# TiltSensor.net
KiCad netlist of a schematic drawn in EAGLE
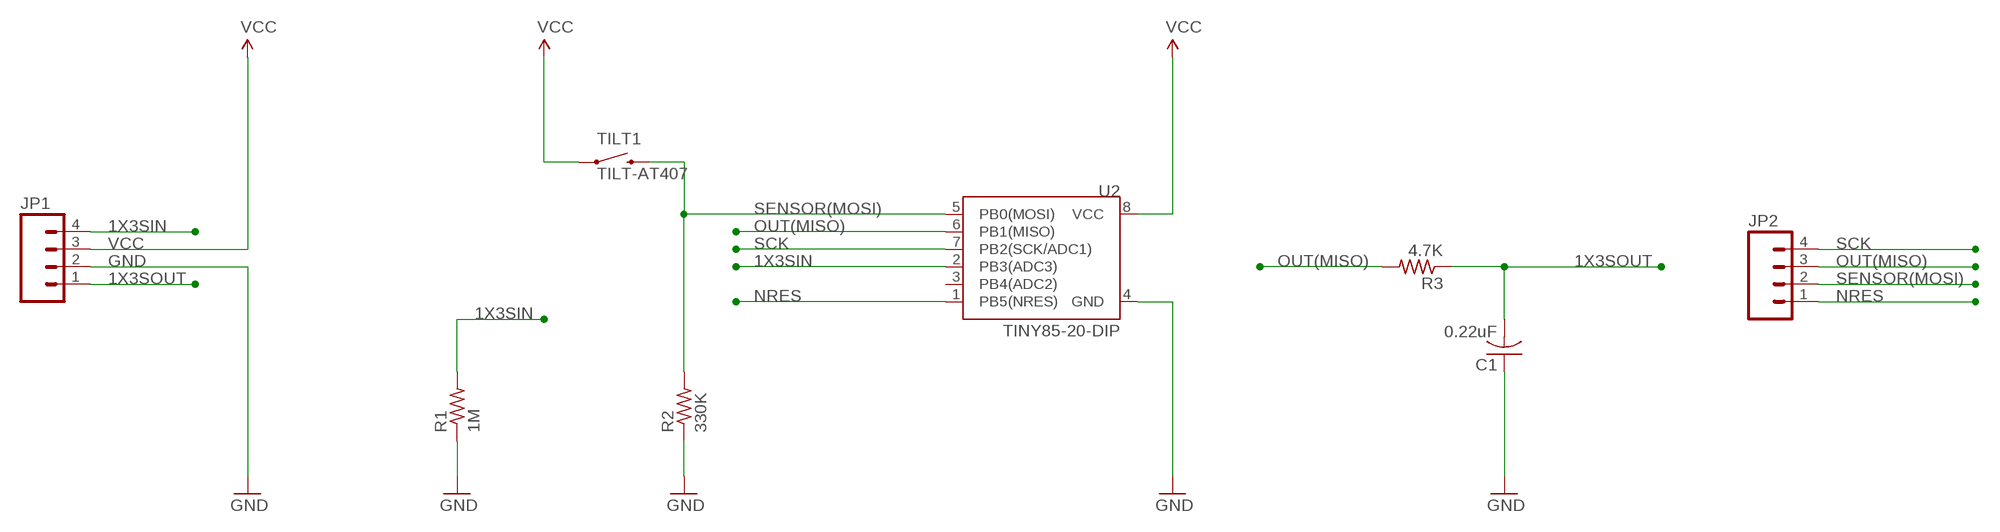
[diagram p0: schematic, sheet 1]

(export (version "E")
  (design (tool "Eeschema 10.0.6"))
  (components
    (comp (ref "C1")
      (value "0.22uF")
      (footprint "eagle-import:C0402")
      (libsource (lib "eagle-import") (part "C-USC0402"))
    )
    (comp (ref "JP1")
      (value "M04PTH")
      (footprint "eagle-import:1X04")
      (libsource (lib "eagle-import") (part "M04PTH"))
    )
    (comp (ref "JP2")
      (value "M04PTH")
      (footprint "eagle-import:1X04")
      (libsource (lib "eagle-import") (part "M04PTH"))
    )
    (comp (ref "R1")
      (value "1M")
      (footprint "eagle-import:R0603")
      (libsource (lib "eagle-import") (part "R-US_R0603"))
    )
    (comp (ref "R2")
      (value "330K")
      (footprint "eagle-import:R0603")
      (libsource (lib "eagle-import") (part "R-US_R0603"))
    )
    (comp (ref "R3")
      (value "4.7K")
      (footprint "eagle-import:R0603")
      (libsource (lib "eagle-import") (part "R-US_R0603"))
    )
    (comp (ref "TILT1")
      (value "TILT-AT407")
      (footprint "eagle-import:TILT-AT407")
      (libsource (lib "eagle-import") (part "TILT-AT407"))
    )
    (comp (ref "U2")
      (value "TINY85-20-DIP")
      (footprint "eagle-import:DIP08")
      (libsource (lib "eagle-import") (part "ATTINY45TINY85-20-DIP"))
    )
  )
  (nets
    (net (code "1") (name "/1X3SIN") (class "Default")
      (node (ref "JP1") (pin "4") (pinfunction "4_4") (pintype "passive"))
      (node (ref "R1") (pin "2") (pinfunction "2_2") (pintype "passive"))
      (node (ref "U2") (pin "2") (pinfunction "PB3(ADC3)_2") (pintype "bidirectional"))
    )
    (net (code "2") (name "/1X3SOUT") (class "Default")
      (node (ref "C1") (pin "2") (pinfunction "2_2") (pintype "passive"))
      (node (ref "JP1") (pin "1") (pinfunction "1_1") (pintype "passive"))
      (node (ref "R3") (pin "1") (pinfunction "1_1") (pintype "passive"))
    )
    (net (code "3") (name "/NRES") (class "Default")
      (node (ref "JP2") (pin "1") (pinfunction "1_1") (pintype "passive"))
      (node (ref "U2") (pin "1") (pinfunction "PB5(NRES)_1") (pintype "bidirectional"))
    )
    (net (code "4") (name "/OUT(MISO)") (class "Default")
      (node (ref "JP2") (pin "3") (pinfunction "3_3") (pintype "passive"))
      (node (ref "R3") (pin "2") (pinfunction "2_2") (pintype "passive"))
      (node (ref "U2") (pin "6") (pinfunction "PB1(MISO)_6") (pintype "bidirectional"))
    )
    (net (code "5") (name "/SCK") (class "Default")
      (node (ref "JP2") (pin "4") (pinfunction "4_4") (pintype "passive"))
      (node (ref "U2") (pin "7") (pinfunction "PB2(SCK/ADC1)_7") (pintype "bidirectional"))
    )
    (net (code "6") (name "/SENSOR(MOSI)") (class "Default")
      (node (ref "JP2") (pin "2") (pinfunction "2_2") (pintype "passive"))
      (node (ref "R2") (pin "2") (pinfunction "2_2") (pintype "passive"))
      (node (ref "TILT1") (pin "P$2") (pinfunction "2_P$2") (pintype "passive"))
      (node (ref "U2") (pin "5") (pinfunction "PB0(MOSI)_5") (pintype "bidirectional"))
    )
    (net (code "7") (name "GND") (class "Default")
      (node (ref "C1") (pin "1") (pinfunction "1_1") (pintype "passive"))
      (node (ref "JP1") (pin "2") (pinfunction "2_2") (pintype "passive"))
      (node (ref "R1") (pin "1") (pinfunction "1_1") (pintype "passive"))
      (node (ref "R2") (pin "1") (pinfunction "1_1") (pintype "passive"))
      (node (ref "U2") (pin "4") (pinfunction "GND_4") (pintype "bidirectional"))
    )
    (net (code "8") (name "VCC") (class "Default")
      (node (ref "JP1") (pin "3") (pinfunction "3_3") (pintype "passive"))
      (node (ref "TILT1") (pin "P$1") (pinfunction "1_P$1") (pintype "passive"))
      (node (ref "U2") (pin "8") (pinfunction "VCC_8") (pintype "bidirectional"))
    )
    (net (code "9") (name "unconnected-(U2-PB4(ADC2)-Pad3)") (class "Default")
      (node (ref "U2") (pin "3") (pinfunction "PB4(ADC2)_3") (pintype "bidirectional"))
    )
  )
)
